# Power.net
KiCad netlist of a schematic drawn in Altium Designer
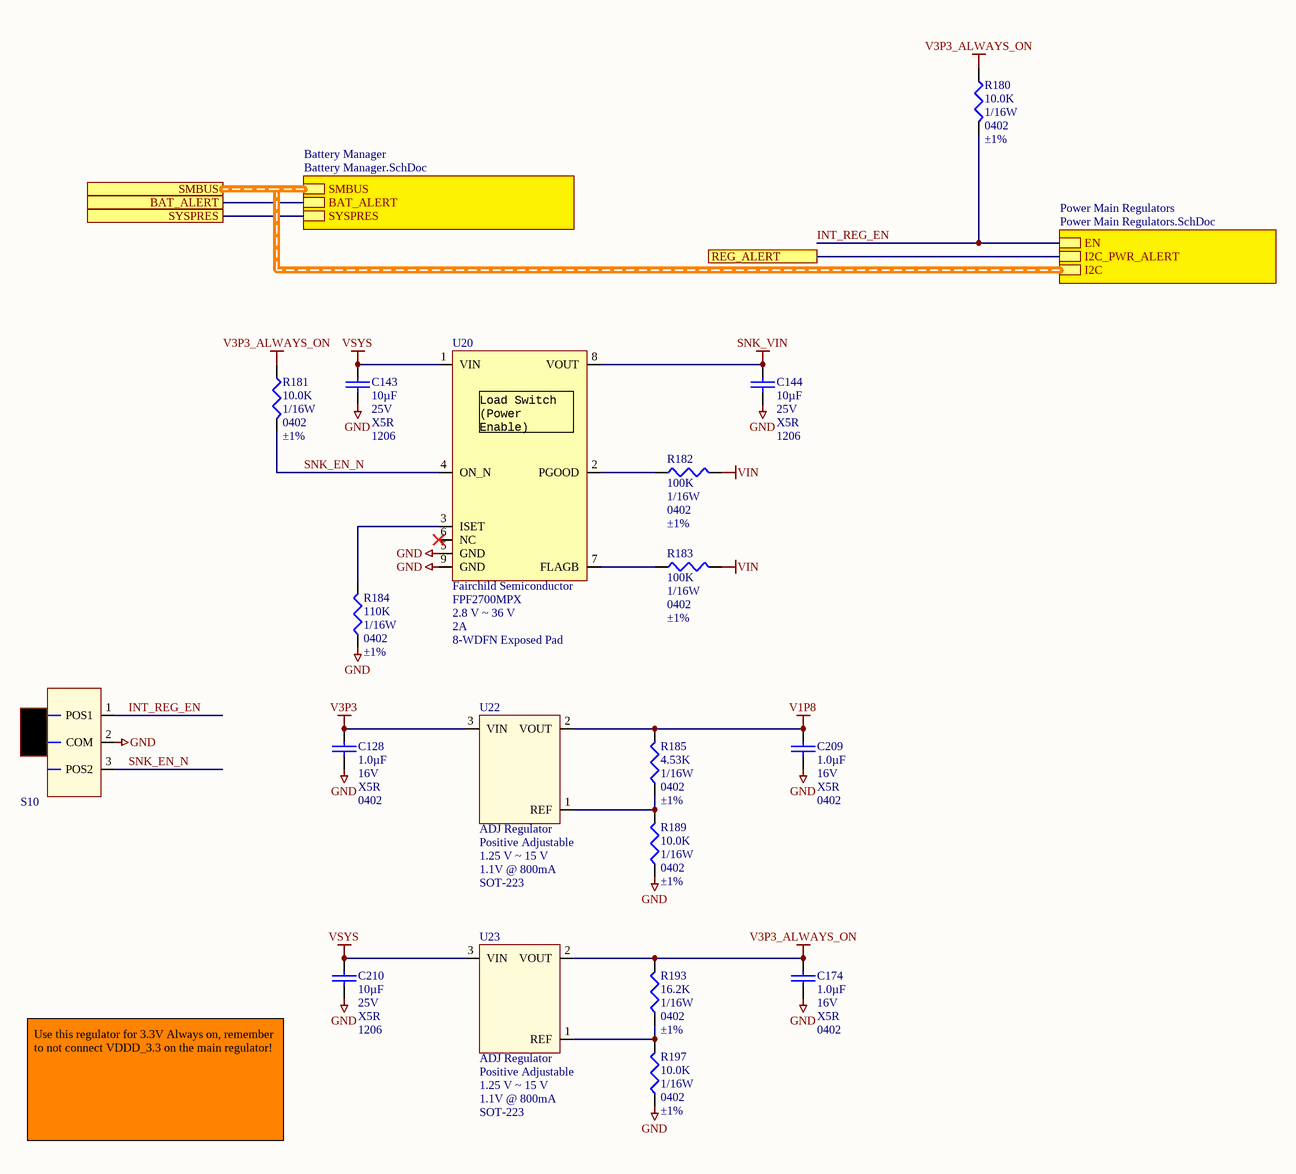
[diagram p0: Power.SchDoc]

(export (version "E")
  (design (tool "Eeschema 10.0.6"))
  (components
    (comp (ref "C128")
      (value "1.0uF")
      (footprint "C_ERA-0402")
      (description "CAP CER 1.0UF 16V X5R 0402")
      (fields
        (field (name "MANUFACTURER") "Taiyo Yuden")
        (field (name "MANUFACTURER PART NUMBER") "EMK105BJ105KV-F")
        (field (name "CAPACITANCE") "1.0µF")
        (field (name "VOLTAGE - RATED") "16V")
        (field (name "TEMPERATURE COEFFICIENT") "X5R")
        (field (name "PACKAGE / CASE") "0402")
      )
      (libsource (lib "Main Library") (part "C_0402_1.0UF_16V"))
    )
    (comp (ref "C143")
      (value "10µF")
      (footprint "CAP-1206")
      (description "CAP CER 10UF 25V X5R 1206")
      (fields
        (field (name "MANUFACTURER") "Murata Electronics North America")
        (field (name "MANUFACTURER PART NUMBER") "GRM31CR61E106MA12L")
        (field (name "CAPACITANCE") "10µF")
        (field (name "VOLTAGE - RATED") "25V")
        (field (name "TEMPERATURE COEFFICIENT") "X5R")
        (field (name "PACKAGE / CASE") "1206")
      )
      (libsource (lib "Main Library") (part "C_1206_10UF_25V"))
    )
    (comp (ref "C144")
      (value "10µF")
      (footprint "CAP-1206")
      (description "CAP CER 10UF 25V X5R 1206")
      (fields
        (field (name "MANUFACTURER") "Murata Electronics North America")
        (field (name "MANUFACTURER PART NUMBER") "GRM31CR61E106MA12L")
        (field (name "CAPACITANCE") "10µF")
        (field (name "VOLTAGE - RATED") "25V")
        (field (name "TEMPERATURE COEFFICIENT") "X5R")
        (field (name "PACKAGE / CASE") "1206")
      )
      (libsource (lib "Main Library") (part "C_1206_10UF_25V"))
    )
    (comp (ref "C174")
      (value "1.0uF")
      (footprint "C_ERA-0402")
      (description "CAP CER 1.0UF 16V X5R 0402")
      (fields
        (field (name "MANUFACTURER") "Taiyo Yuden")
        (field (name "MANUFACTURER PART NUMBER") "EMK105BJ105KV-F")
        (field (name "CAPACITANCE") "1.0µF")
        (field (name "VOLTAGE - RATED") "16V")
        (field (name "TEMPERATURE COEFFICIENT") "X5R")
        (field (name "PACKAGE / CASE") "0402")
      )
      (libsource (lib "Main Library") (part "C_0402_1.0UF_16V"))
    )
    (comp (ref "C209")
      (value "1.0uF")
      (footprint "C_ERA-0402")
      (description "CAP CER 1.0UF 16V X5R 0402")
      (fields
        (field (name "MANUFACTURER") "Taiyo Yuden")
        (field (name "MANUFACTURER PART NUMBER") "EMK105BJ105KV-F")
        (field (name "CAPACITANCE") "1.0µF")
        (field (name "VOLTAGE - RATED") "16V")
        (field (name "TEMPERATURE COEFFICIENT") "X5R")
        (field (name "PACKAGE / CASE") "0402")
      )
      (libsource (lib "Main Library") (part "C_0402_1.0UF_16V"))
    )
    (comp (ref "C210")
      (value "10µF")
      (footprint "CAP-1206")
      (description "CAP CER 10UF 25V X5R 1206")
      (fields
        (field (name "MANUFACTURER") "Murata Electronics North America")
        (field (name "MANUFACTURER PART NUMBER") "GRM31CR61E106MA12L")
        (field (name "CAPACITANCE") "10µF")
        (field (name "VOLTAGE - RATED") "25V")
        (field (name "TEMPERATURE COEFFICIENT") "X5R")
        (field (name "PACKAGE / CASE") "1206")
      )
      (libsource (lib "Main Library") (part "C_1206_10UF_25V"))
    )
    (comp (ref "R180")
      (value "R_0402_10.0K")
      (footprint "R_0402")
      (description "RES 10.0K OHM 1/16W 1% 0402 SMD")
      (fields
        (field (name "MANUFACTURER") "Stackpole Electronics Inc")
        (field (name "MANUFACTURER PART NUMBER") "RMCF0402FT10K0")
        (field (name "RESISTANCE IN OHMS") "10.0K")
        (field (name "POWER (WATTS)") "1/16W")
        (field (name "CASE") "0402")
        (field (name "TOLERANCE") "±1%")
      )
      (libsource (lib "Cospan Design") (part "R_0402_10.0K"))
    )
    (comp (ref "R181")
      (value "R_0402_10.0K")
      (footprint "R_0402")
      (description "RES 10.0K OHM 1/16W 1% 0402 SMD")
      (fields
        (field (name "MANUFACTURER") "Stackpole Electronics Inc")
        (field (name "MANUFACTURER PART NUMBER") "RMCF0402FT10K0")
        (field (name "RESISTANCE IN OHMS") "10.0K")
        (field (name "POWER (WATTS)") "1/16W")
        (field (name "CASE") "0402")
        (field (name "TOLERANCE") "±1%")
      )
      (libsource (lib "Cospan Design") (part "R_0402_10.0K"))
    )
    (comp (ref "R182")
      (value "R_0402_100K")
      (footprint "R_0402")
      (description "RES SMD 100K OHM 1% 1/16W 0402")
      (fields
        (field (name "MANUFACTURER") "Yageo")
        (field (name "MANUFACTURER PART NUMBER") "RC0402FR-07100KL")
        (field (name "RESISTANCE IN OHMS") "100K")
        (field (name "POWER (WATTS)") "1/16W")
        (field (name "CASE") "0402")
        (field (name "TOLERANCE") "±1%")
      )
      (libsource (lib "Cospan Design") (part "R_0402_100K"))
    )
    (comp (ref "R183")
      (value "R_0402_100K")
      (footprint "R_0402")
      (description "RES SMD 100K OHM 1% 1/16W 0402")
      (fields
        (field (name "MANUFACTURER") "Yageo")
        (field (name "MANUFACTURER PART NUMBER") "RC0402FR-07100KL")
        (field (name "RESISTANCE IN OHMS") "100K")
        (field (name "POWER (WATTS)") "1/16W")
        (field (name "CASE") "0402")
        (field (name "TOLERANCE") "±1%")
      )
      (libsource (lib "Cospan Design") (part "R_0402_100K"))
    )
    (comp (ref "R184")
      (value "110K")
      (footprint "R_0402")
      (description "RES 110K OHM 1/10W 1% 0402 SMD")
      (fields
        (field (name "MANUFACTURER") "Panasonic Electronic Components")
        (field (name "MANUFACTURER PART NUMBER") "ERJ-2RKF1103X")
        (field (name "RESISTANCE IN OHMS") "110K")
        (field (name "POWER (WATTS)") "1/16W")
        (field (name "CASE") "0402")
        (field (name "TOLERANCE") "±1%")
      )
      (libsource (lib "Main Library") (part "R_0402_110K"))
    )
    (comp (ref "R185")
      (value "4.53k Ohms")
      (footprint "R_0402")
      (description "RES 4.53K OHM 1/16W 1% 0402 SMD")
      (fields
        (field (name "MANUFACTURER") "Vishay/Dale")
        (field (name "MANUFACTURER PART NUMBER") "CRCW04024K53FKED")
        (field (name "RESISTANCE IN OHMS") "4.53K")
        (field (name "POWER (WATTS)") "1/16W")
        (field (name "CASE") "0402")
        (field (name "TOLERANCE") "±1%")
      )
      (libsource (lib "Main Library") (part "R_0402_4.53K"))
    )
    (comp (ref "R189")
      (value "R_0402_10.0K")
      (footprint "R_0402")
      (description "RES 10.0K OHM 1/16W 1% 0402 SMD")
      (fields
        (field (name "MANUFACTURER") "Stackpole Electronics Inc")
        (field (name "MANUFACTURER PART NUMBER") "RMCF0402FT10K0")
        (field (name "RESISTANCE IN OHMS") "10.0K")
        (field (name "POWER (WATTS)") "1/16W")
        (field (name "CASE") "0402")
        (field (name "TOLERANCE") "±1%")
      )
      (libsource (lib "Cospan Design") (part "R_0402_10.0K"))
    )
    (comp (ref "R193")
      (value "R_0402_16.2K")
      (footprint "R_0402")
      (description "RES 16.2K OHM 1/16W 1% 0402 SMD")
      (fields
        (field (name "MANUFACTURER") "Yageo")
        (field (name "MANUFACTURER PART NUMBER") "RC0402FR-0716K2L")
        (field (name "RESISTANCE IN OHMS") "16.2K")
        (field (name "POWER (WATTS)") "1/16W")
        (field (name "CASE") "0402")
        (field (name "TOLERANCE") "±1%")
      )
      (libsource (lib "Main Library") (part "R_0402_16.2K"))
    )
    (comp (ref "R197")
      (value "R_0402_10.0K")
      (footprint "R_0402")
      (description "RES 10.0K OHM 1/16W 1% 0402 SMD")
      (fields
        (field (name "MANUFACTURER") "Stackpole Electronics Inc")
        (field (name "MANUFACTURER PART NUMBER") "RMCF0402FT10K0")
        (field (name "RESISTANCE IN OHMS") "10.0K")
        (field (name "POWER (WATTS)") "1/16W")
        (field (name "CASE") "0402")
        (field (name "TOLERANCE") "±1%")
      )
      (libsource (lib "Cospan Design") (part "R_0402_10.0K"))
    )
    (comp (ref "S10")
      (value "Micro Slide Switch")
      (footprint "PCM_SMD_SWITCH")
      (description "SWITCH SLIDE SPDT 300MA 6V")
      (fields
        (field (name "MANUFACTURER") "C&K Components")
        (field (name "MANUFACTURER PART NUMBER") "PCM12SMTR")
      )
      (libsource (lib "Cospan Design") (part "S_MICRO_SLIDE_SWITCH_ON_OFF"))
    )
    (comp (ref "U20")
      (value "U_FPF2700MPX")
      (footprint "SON65P300X80_HS-9N")
      (description "IC LOAD SWITCH CURR LIMIT 8-MLP")
      (fields
        (field (name "MANUFACTURER") "Fairchild Semiconductor")
        (field (name "MANUFACTURER PART NUMBER") "FPF2700MPX")
        (field (name "VOLTAGE - LOAD") "2.8 V ~ 36 V")
        (field (name "CURRENT - OUTPUT (MAX)") "2A")
        (field (name "PACKAGE / CASE") "8-WDFN Exposed Pad")
      )
      (libsource (lib "Cospan Design") (part "U_FPF2700MPX"))
    )
    (comp (ref "U22")
      (value "ADJ Regulator")
      (footprint "SOT230P700X180-4N")
      (description "IC REG LDO ADJ 950MA SOT-223")
      (fields
        (field (name "MANUFACTURER") "STMicroelectronics")
        (field (name "MANUFACTURER PART NUMBER") "LD1117STR")
        (field (name "REGULATOR TOPOLOGY") "Positive Adjustable")
        (field (name "VOLTAGE - OUTPUT") "1.25 V ~ 15 V")
        (field (name "VOLTAGE - DROPOUT (TYPICAL)") "1.1V @ 800mA")
        (field (name "SUPPLIER DEVICE PACKAGE") "SOT-223")
      )
      (libsource (lib "Main Library") (part "U_LD117STR"))
    )
    (comp (ref "U23")
      (value "ADJ Regulator")
      (footprint "SOT230P700X180-4N")
      (description "IC REG LDO ADJ 950MA SOT-223")
      (fields
        (field (name "MANUFACTURER") "STMicroelectronics")
        (field (name "MANUFACTURER PART NUMBER") "LD1117STR")
        (field (name "REGULATOR TOPOLOGY") "Positive Adjustable")
        (field (name "VOLTAGE - OUTPUT") "1.25 V ~ 15 V")
        (field (name "VOLTAGE - DROPOUT (TYPICAL)") "1.1V @ 800mA")
        (field (name "SUPPLIER DEVICE PACKAGE") "SOT-223")
      )
      (libsource (lib "Main Library") (part "U_LD117STR"))
    )
  )
  (nets
    (net (code "4") (name "/INT_REG_EN") (class "Default")
      (node (ref "R180") (pin "1") (pinfunction "1_1") (pintype "passive"))
      (node (ref "S10") (pin "1") (pinfunction "POS1_1") (pintype "passive"))
    )
    (net (code "7") (name "/SNK_EN_N") (class "Default")
      (node (ref "R181") (pin "1") (pinfunction "1_1") (pintype "passive"))
      (node (ref "S10") (pin "3") (pinfunction "POS2_3") (pintype "passive"))
      (node (ref "U20") (pin "4") (pinfunction "ON_N_4") (pintype "passive"))
    )
    (net (code "9") (name "GND") (class "Default")
      (node (ref "C128") (pin "1") (pinfunction "1_1") (pintype "passive"))
      (node (ref "C143") (pin "1") (pinfunction "1_1") (pintype "passive"))
      (node (ref "C144") (pin "1") (pinfunction "1_1") (pintype "passive"))
      (node (ref "C174") (pin "1") (pinfunction "1_1") (pintype "passive"))
      (node (ref "C209") (pin "1") (pinfunction "1_1") (pintype "passive"))
      (node (ref "C210") (pin "1") (pinfunction "1_1") (pintype "passive"))
      (node (ref "R184") (pin "2") (pinfunction "2_2") (pintype "passive"))
      (node (ref "R189") (pin "2") (pinfunction "2_2") (pintype "passive"))
      (node (ref "R197") (pin "2") (pinfunction "2_2") (pintype "passive"))
      (node (ref "S10") (pin "2") (pinfunction "COM_2") (pintype "passive"))
      (node (ref "U20") (pin "5") (pinfunction "GND_5") (pintype "passive"))
      (node (ref "U20") (pin "9") (pinfunction "GND_9") (pintype "passive"))
    )
    (net (code "10") (name "Net-(U20-FLAGB)") (class "Default")
      (node (ref "R183") (pin "2") (pinfunction "2_2") (pintype "passive"))
      (node (ref "U20") (pin "7") (pinfunction "FLAGB_7") (pintype "passive"))
    )
    (net (code "11") (name "Net-(U20-ISET)") (class "Default")
      (node (ref "R184") (pin "1") (pinfunction "1_1") (pintype "passive"))
      (node (ref "U20") (pin "3") (pinfunction "ISET_3") (pintype "passive"))
    )
    (net (code "12") (name "Net-(U20-PGOOD)") (class "Default")
      (node (ref "R182") (pin "2") (pinfunction "2_2") (pintype "passive"))
      (node (ref "U20") (pin "2") (pinfunction "PGOOD_2") (pintype "passive"))
    )
    (net (code "13") (name "Net-(U22-REF)") (class "Default")
      (node (ref "R185") (pin "2") (pinfunction "2_2") (pintype "passive"))
      (node (ref "R189") (pin "1") (pinfunction "1_1") (pintype "passive"))
      (node (ref "U22") (pin "1") (pinfunction "REF_1") (pintype "passive"))
    )
    (net (code "14") (name "Net-(U23-REF)") (class "Default")
      (node (ref "R193") (pin "2") (pinfunction "2_2") (pintype "passive"))
      (node (ref "R197") (pin "1") (pinfunction "1_1") (pintype "passive"))
      (node (ref "U23") (pin "1") (pinfunction "REF_1") (pintype "passive"))
    )
    (net (code "15") (name "SNK_VIN") (class "Default")
      (node (ref "C144") (pin "2") (pinfunction "2_2") (pintype "passive"))
      (node (ref "U20") (pin "8") (pinfunction "VOUT_8") (pintype "passive"))
    )
    (net (code "16") (name "V1P8") (class "Default")
      (node (ref "C209") (pin "2") (pinfunction "2_2") (pintype "passive"))
      (node (ref "R185") (pin "1") (pinfunction "1_1") (pintype "passive"))
      (node (ref "U22") (pin "2") (pinfunction "VOUT_2") (pintype "passive"))
    )
    (net (code "17") (name "V3P3") (class "Default")
      (node (ref "C128") (pin "2") (pinfunction "2_2") (pintype "passive"))
      (node (ref "U22") (pin "3") (pinfunction "VIN_3") (pintype "passive"))
    )
    (net (code "18") (name "V3P3_ALWAYS_ON") (class "Default")
      (node (ref "C174") (pin "2") (pinfunction "2_2") (pintype "passive"))
      (node (ref "R180") (pin "2") (pinfunction "2_2") (pintype "passive"))
      (node (ref "R181") (pin "2") (pinfunction "2_2") (pintype "passive"))
      (node (ref "R193") (pin "1") (pinfunction "1_1") (pintype "passive"))
      (node (ref "U23") (pin "2") (pinfunction "VOUT_2") (pintype "passive"))
    )
    (net (code "19") (name "VIN") (class "Default")
      (node (ref "R182") (pin "1") (pinfunction "1_1") (pintype "passive"))
      (node (ref "R183") (pin "1") (pinfunction "1_1") (pintype "passive"))
    )
    (net (code "20") (name "VSYS") (class "Default")
      (node (ref "C143") (pin "2") (pinfunction "2_2") (pintype "passive"))
      (node (ref "C210") (pin "2") (pinfunction "2_2") (pintype "passive"))
      (node (ref "U20") (pin "1") (pinfunction "VIN_1") (pintype "passive"))
      (node (ref "U23") (pin "3") (pinfunction "VIN_3") (pintype "passive"))
    )
    (net (code "21") (name "unconnected-(U20-NC-Pad6)") (class "Default")
      (node (ref "U20") (pin "6") (pinfunction "NC_6") (pintype "passive+no_connect"))
    )
  )
)
